# Trial.net
KiCad netlist of a schematic drawn in EAGLE
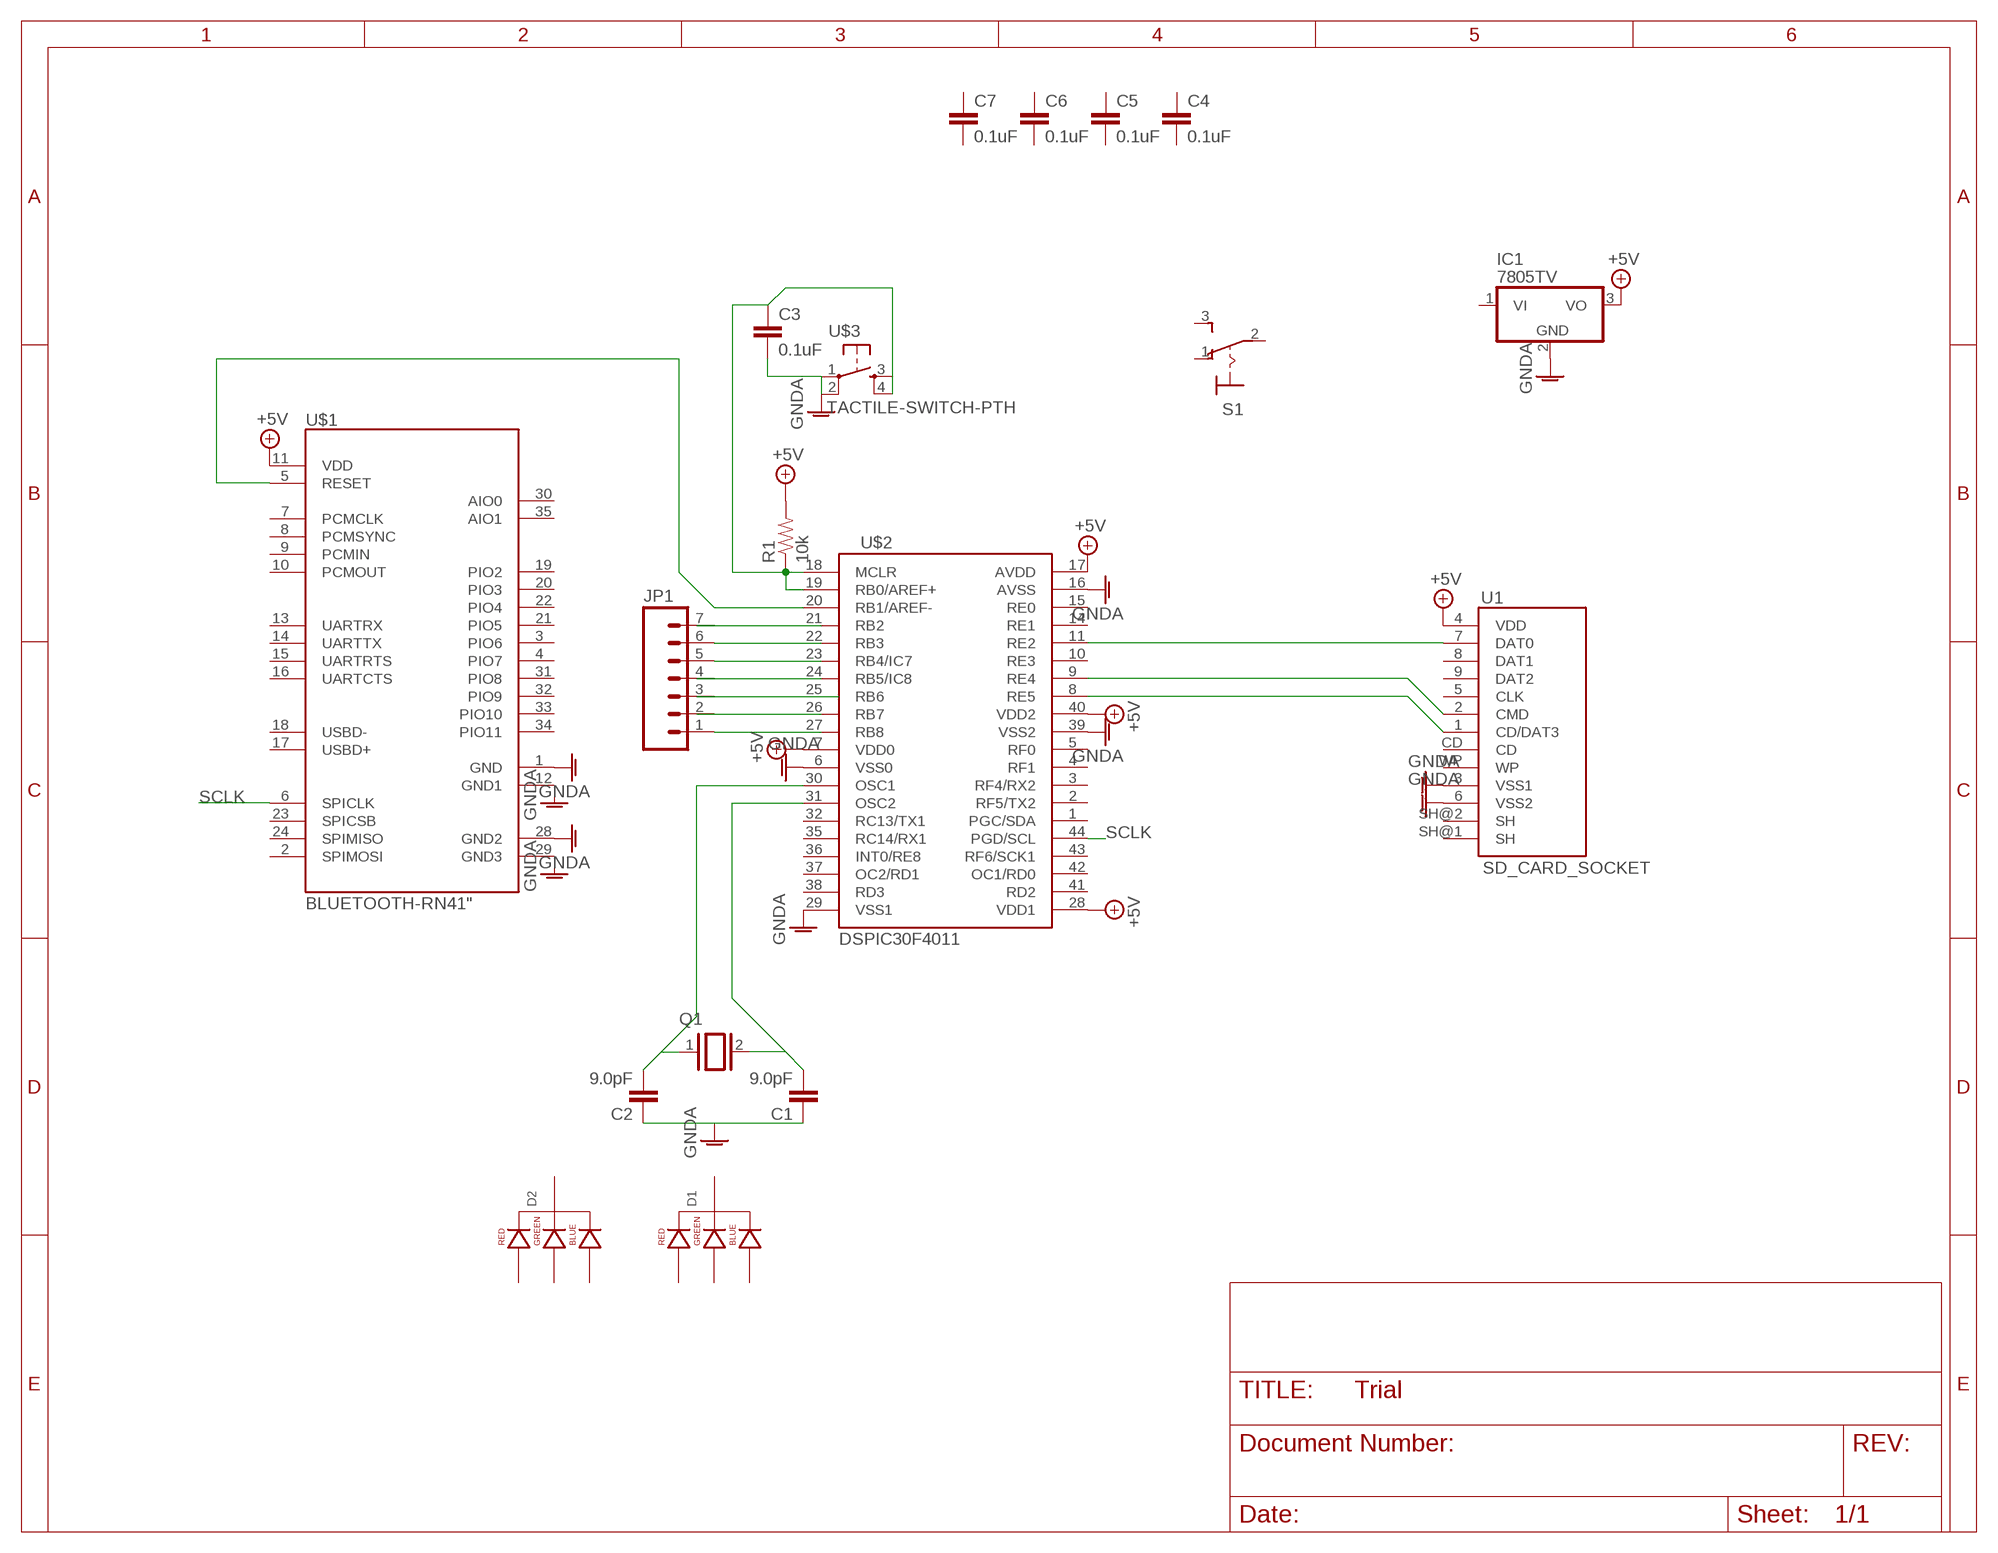
[diagram p0: schematic, sheet 1]

(export (version "E")
  (design (tool "Eeschema 10.0.6"))
  (components
    (comp (ref "C1")
      (value "9.0pF")
      (footprint "eagle-import:0603-CAP")
      (libsource (lib "eagle-import") (part "9.0PF-50V-10%(0603)"))
    )
    (comp (ref "C2")
      (value "9.0pF")
      (footprint "eagle-import:0603-CAP")
      (libsource (lib "eagle-import") (part "9.0PF-50V-10%(0603)"))
    )
    (comp (ref "C3")
      (value "0.1uF")
      (footprint "eagle-import:0402-CAP")
      (libsource (lib "eagle-import") (part "0.1UF-16V(+-10%)(0402)"))
    )
    (comp (ref "C4")
      (value "0.1uF")
      (footprint "eagle-import:0402-CAP")
      (libsource (lib "eagle-import") (part "0.1UF-16V(+-10%)(0402)"))
    )
    (comp (ref "C5")
      (value "0.1uF")
      (footprint "eagle-import:0402-CAP")
      (libsource (lib "eagle-import") (part "0.1UF-16V(+-10%)(0402)"))
    )
    (comp (ref "C6")
      (value "0.1uF")
      (footprint "eagle-import:0402-CAP")
      (libsource (lib "eagle-import") (part "0.1UF-16V(+-10%)(0402)"))
    )
    (comp (ref "C7")
      (value "0.1uF")
      (footprint "eagle-import:0402-CAP")
      (libsource (lib "eagle-import") (part "0.1UF-16V(+-10%)(0402)"))
    )
    (comp (ref "D1")
      (value "LED-RGB-CC-THRUCLEAR")
      (footprint "eagle-import:LED-RGB-THRU")
      (libsource (lib "eagle-import") (part "LED-RGB-CC-THRUCLEAR"))
    )
    (comp (ref "D2")
      (value "LED-RGB-CC-THRUCLEAR")
      (footprint "eagle-import:LED-RGB-THRU")
      (libsource (lib "eagle-import") (part "LED-RGB-CC-THRUCLEAR"))
    )
    (comp (ref "IC1")
      (value "7805TV")
      (footprint "eagle-import:TO220V")
      (libsource (lib "eagle-import") (part "78TV05"))
    )
    (comp (ref "JP1")
      (value "M07LONGPADS")
      (footprint "eagle-import:1X07_LONGPADS")
      (libsource (lib "eagle-import") (part "M07LONGPADS"))
    )
    (comp (ref "Q1")
      (value "XTAL")
      (footprint "eagle-import:Q")
      (libsource (lib "eagle-import") (part "XTAL"))
    )
    (comp (ref "R1")
      (value "10k")
      (footprint "eagle-import:AXIAL-0.3")
      (libsource (lib "eagle-import") (part "10KOHM-1/4W-1%(PTH)HORIZ"))
    )
    (comp (ref "S1")
      (value "320-916")
      (footprint "eagle-import:320-916")
      (libsource (lib "eagle-import") (part "320-916"))
    )
    (comp (ref "U$1")
      (value "BLUETOOTH-RN41\"")
      (footprint "eagle-import:RN41")
      (libsource (lib "eagle-import") (part "BLUETOOTH-RN41{dblquote}"))
    )
    (comp (ref "U$2")
      (value "DSPIC30F4011")
      (footprint "eagle-import:TQFP44")
      (libsource (lib "eagle-import") (part "DSPIC30F4011"))
    )
    (comp (ref "U$3")
      (value "TACTILE-SWITCH-PTH")
      (footprint "eagle-import:TAC-SWITCH-PTH")
      (libsource (lib "eagle-import") (part "TACTILE-SWITCH-PTH"))
    )
    (comp (ref "U1")
      (value "SD_CARD_SOCKET")
      (footprint "eagle-import:SD_1_1")
      (libsource (lib "eagle-import") (part "SD_CARD_SOCKET"))
    )
  )
  (nets
    (net (code "1") (name "+5V") (class "Default")
      (node (ref "IC1") (pin "3") (pinfunction "VO_3") (pintype "passive"))
      (node (ref "R1") (pin "P$2") (pinfunction "2_P$2") (pintype "passive"))
      (node (ref "U$1") (pin "11") (pinfunction "VDD_11") (pintype "bidirectional"))
      (node (ref "U$2") (pin "17") (pinfunction "AVDD_17") (pintype "bidirectional"))
      (node (ref "U$2") (pin "28") (pinfunction "VDD1_28") (pintype "bidirectional"))
      (node (ref "U$2") (pin "40") (pinfunction "VDD2_40") (pintype "bidirectional"))
      (node (ref "U$2") (pin "7") (pinfunction "VDD0_7") (pintype "bidirectional"))
      (node (ref "U1") (pin "4") (pinfunction "VDD_4") (pintype "power_in"))
    )
    (net (code "2") (name "/SCLK") (class "Default")
      (node (ref "U$1") (pin "6") (pinfunction "SPICLK_6") (pintype "bidirectional"))
      (node (ref "U$2") (pin "44") (pinfunction "PGD/SCL_44") (pintype "bidirectional"))
    )
    (net (code "3") (name "GNDA") (class "Default")
      (node (ref "C1") (pin "1") (pinfunction "1_1") (pintype "passive"))
      (node (ref "C2") (pin "1") (pinfunction "1_1") (pintype "passive"))
      (node (ref "C3") (pin "2") (pinfunction "2_2") (pintype "passive"))
      (node (ref "IC1") (pin "2") (pinfunction "GND_2") (pintype "passive"))
      (node (ref "U$1") (pin "1") (pinfunction "GND_1") (pintype "bidirectional"))
      (node (ref "U$1") (pin "12") (pinfunction "GND1_12") (pintype "bidirectional"))
      (node (ref "U$1") (pin "28") (pinfunction "GND2_28") (pintype "bidirectional"))
      (node (ref "U$1") (pin "29") (pinfunction "GND3_29") (pintype "bidirectional"))
      (node (ref "U$2") (pin "16") (pinfunction "AVSS_16") (pintype "bidirectional"))
      (node (ref "U$2") (pin "29") (pinfunction "VSS1_29") (pintype "bidirectional"))
      (node (ref "U$2") (pin "39") (pinfunction "VSS2_39") (pintype "bidirectional"))
      (node (ref "U$2") (pin "6") (pinfunction "VSS0_6") (pintype "bidirectional"))
      (node (ref "U$3") (pin "1") (pinfunction "1_1") (pintype "passive"))
      (node (ref "U$3") (pin "2") (pinfunction "2_2") (pintype "passive"))
      (node (ref "U1") (pin "3") (pinfunction "VSS1_3") (pintype "power_in"))
      (node (ref "U1") (pin "6") (pinfunction "VSS2_6") (pintype "power_in"))
    )
    (net (code "4") (name "Net-(R1-1)") (class "Default")
      (node (ref "C3") (pin "1") (pinfunction "1_1") (pintype "passive"))
      (node (ref "R1") (pin "P$1") (pinfunction "1_P$1") (pintype "passive"))
      (node (ref "U$2") (pin "18") (pinfunction "MCLR_18") (pintype "bidirectional"))
      (node (ref "U$2") (pin "19") (pinfunction "RB0/AREF+_19") (pintype "bidirectional"))
      (node (ref "U$3") (pin "3") (pinfunction "3_3") (pintype "passive"))
      (node (ref "U$3") (pin "4") (pinfunction "4_4") (pintype "passive"))
    )
    (net (code "5") (name "Net-(U$1-RESET)") (class "Default")
      (node (ref "U$1") (pin "5") (pinfunction "RESET_5") (pintype "bidirectional"))
      (node (ref "U$2") (pin "20") (pinfunction "RB1/AREF-_20") (pintype "bidirectional"))
    )
    (net (code "6") (name "Net-(U$2-OSC1)") (class "Default")
      (node (ref "C2") (pin "2") (pinfunction "2_2") (pintype "passive"))
      (node (ref "Q1") (pin "1") (pinfunction "1_1") (pintype "passive"))
      (node (ref "U$2") (pin "30") (pinfunction "OSC1_30") (pintype "bidirectional"))
    )
    (net (code "7") (name "Net-(U$2-OSC2)") (class "Default")
      (node (ref "C1") (pin "2") (pinfunction "2_2") (pintype "passive"))
      (node (ref "Q1") (pin "2") (pinfunction "2_2") (pintype "passive"))
      (node (ref "U$2") (pin "31") (pinfunction "OSC2_31") (pintype "bidirectional"))
    )
    (net (code "8") (name "Net-(U$2-RE2)") (class "Default")
      (node (ref "U$2") (pin "11") (pinfunction "RE2_11") (pintype "bidirectional"))
      (node (ref "U1") (pin "7") (pinfunction "DAT0_7") (pintype "bidirectional"))
    )
    (net (code "9") (name "Net-(U$2-RE4)") (class "Default")
      (node (ref "U$2") (pin "9") (pinfunction "RE4_9") (pintype "bidirectional"))
      (node (ref "U1") (pin "2") (pinfunction "CMD_2") (pintype "bidirectional"))
    )
    (net (code "10") (name "Net-(U$2-RE5)") (class "Default")
      (node (ref "U$2") (pin "8") (pinfunction "RE5_8") (pintype "bidirectional"))
      (node (ref "U1") (pin "1") (pinfunction "CD/DAT3_1") (pintype "bidirectional"))
    )
    (net (code "11") (name "unconnected-(C4-Pad1)") (class "Default")
      (node (ref "C4") (pin "1") (pinfunction "1_1") (pintype "passive"))
    )
    (net (code "12") (name "unconnected-(C4-Pad2)") (class "Default")
      (node (ref "C4") (pin "2") (pinfunction "2_2") (pintype "passive"))
    )
    (net (code "13") (name "unconnected-(C5-Pad1)") (class "Default")
      (node (ref "C5") (pin "1") (pinfunction "1_1") (pintype "passive"))
    )
    (net (code "14") (name "unconnected-(C5-Pad2)") (class "Default")
      (node (ref "C5") (pin "2") (pinfunction "2_2") (pintype "passive"))
    )
    (net (code "15") (name "unconnected-(C6-Pad1)") (class "Default")
      (node (ref "C6") (pin "1") (pinfunction "1_1") (pintype "passive"))
    )
    (net (code "16") (name "unconnected-(C6-Pad2)") (class "Default")
      (node (ref "C6") (pin "2") (pinfunction "2_2") (pintype "passive"))
    )
    (net (code "17") (name "unconnected-(C7-Pad1)") (class "Default")
      (node (ref "C7") (pin "1") (pinfunction "1_1") (pintype "passive"))
    )
    (net (code "18") (name "unconnected-(C7-Pad2)") (class "Default")
      (node (ref "C7") (pin "2") (pinfunction "2_2") (pintype "passive"))
    )
    (net (code "19") (name "unconnected-(D1-BLUE_CATHODE-Pad4)") (class "Default")
      (node (ref "D1") (pin "4") (pinfunction "BLUE_CATHODE_4") (pintype "bidirectional"))
    )
    (net (code "20") (name "unconnected-(D1-CATHODE-Pad2)") (class "Default")
      (node (ref "D1") (pin "2") (pinfunction "CATHODE_2") (pintype "bidirectional"))
    )
    (net (code "21") (name "unconnected-(D1-GREEN_CATHODE-Pad3)") (class "Default")
      (node (ref "D1") (pin "3") (pinfunction "GREEN_CATHODE_3") (pintype "bidirectional"))
    )
    (net (code "22") (name "unconnected-(D1-RED_CATHODE-Pad1)") (class "Default")
      (node (ref "D1") (pin "1") (pinfunction "RED_CATHODE_1") (pintype "bidirectional"))
    )
    (net (code "23") (name "unconnected-(D2-BLUE_CATHODE-Pad4)") (class "Default")
      (node (ref "D2") (pin "4") (pinfunction "BLUE_CATHODE_4") (pintype "bidirectional"))
    )
    (net (code "24") (name "unconnected-(D2-CATHODE-Pad2)") (class "Default")
      (node (ref "D2") (pin "2") (pinfunction "CATHODE_2") (pintype "bidirectional"))
    )
    (net (code "25") (name "unconnected-(D2-GREEN_CATHODE-Pad3)") (class "Default")
      (node (ref "D2") (pin "3") (pinfunction "GREEN_CATHODE_3") (pintype "bidirectional"))
    )
    (net (code "26") (name "unconnected-(D2-RED_CATHODE-Pad1)") (class "Default")
      (node (ref "D2") (pin "1") (pinfunction "RED_CATHODE_1") (pintype "bidirectional"))
    )
    (net (code "27") (name "unconnected-(IC1-VI-Pad1)") (class "Default")
      (node (ref "IC1") (pin "1") (pinfunction "VI_1") (pintype "input"))
    )
    (net (code "28") (name "unconnected-(JP1-Pad1)") (class "Default")
      (node (ref "JP1") (pin "1") (pinfunction "1_1") (pintype "passive"))
    )
    (net (code "29") (name "unconnected-(JP1-Pad2)") (class "Default")
      (node (ref "JP1") (pin "2") (pinfunction "2_2") (pintype "passive"))
    )
    (net (code "30") (name "unconnected-(JP1-Pad3)") (class "Default")
      (node (ref "JP1") (pin "3") (pinfunction "3_3") (pintype "passive"))
    )
    (net (code "31") (name "unconnected-(JP1-Pad4)") (class "Default")
      (node (ref "JP1") (pin "4") (pinfunction "4_4") (pintype "passive"))
    )
    (net (code "32") (name "unconnected-(JP1-Pad5)") (class "Default")
      (node (ref "JP1") (pin "5") (pinfunction "5_5") (pintype "passive"))
    )
    (net (code "33") (name "unconnected-(JP1-Pad6)") (class "Default")
      (node (ref "JP1") (pin "6") (pinfunction "6_6") (pintype "passive"))
    )
    (net (code "34") (name "unconnected-(JP1-Pad7)") (class "Default")
      (node (ref "JP1") (pin "7") (pinfunction "7_7") (pintype "passive"))
    )
    (net (code "35") (name "unconnected-(S1-O-Pad1)") (class "Default")
      (node (ref "S1") (pin "1") (pinfunction "O_1") (pintype "passive"))
    )
    (net (code "36") (name "unconnected-(S1-P-Pad2)") (class "Default")
      (node (ref "S1") (pin "2") (pinfunction "P_2") (pintype "passive"))
    )
    (net (code "37") (name "unconnected-(S1-S-Pad3)") (class "Default")
      (node (ref "S1") (pin "3") (pinfunction "S_3") (pintype "passive"))
    )
    (net (code "38") (name "unconnected-(U$1-AIO0-Pad30)") (class "Default")
      (node (ref "U$1") (pin "30") (pinfunction "AIO0_30") (pintype "bidirectional"))
    )
    (net (code "39") (name "unconnected-(U$1-AIO1-Pad35)") (class "Default")
      (node (ref "U$1") (pin "35") (pinfunction "AIO1_35") (pintype "bidirectional"))
    )
    (net (code "40") (name "unconnected-(U$1-PCMCLK-Pad7)") (class "Default")
      (node (ref "U$1") (pin "7") (pinfunction "PCMCLK_7") (pintype "bidirectional"))
    )
    (net (code "41") (name "unconnected-(U$1-PCMIN-Pad9)") (class "Default")
      (node (ref "U$1") (pin "9") (pinfunction "PCMIN_9") (pintype "bidirectional"))
    )
    (net (code "42") (name "unconnected-(U$1-PCMOUT-Pad10)") (class "Default")
      (node (ref "U$1") (pin "10") (pinfunction "PCMOUT_10") (pintype "bidirectional"))
    )
    (net (code "43") (name "unconnected-(U$1-PCMSYNC-Pad8)") (class "Default")
      (node (ref "U$1") (pin "8") (pinfunction "PCMSYNC_8") (pintype "bidirectional"))
    )
    (net (code "44") (name "unconnected-(U$1-PIO2-Pad19)") (class "Default")
      (node (ref "U$1") (pin "19") (pinfunction "PIO2_19") (pintype "bidirectional"))
    )
    (net (code "45") (name "unconnected-(U$1-PIO3-Pad20)") (class "Default")
      (node (ref "U$1") (pin "20") (pinfunction "PIO3_20") (pintype "bidirectional"))
    )
    (net (code "46") (name "unconnected-(U$1-PIO4-Pad22)") (class "Default")
      (node (ref "U$1") (pin "22") (pinfunction "PIO4_22") (pintype "bidirectional"))
    )
    (net (code "47") (name "unconnected-(U$1-PIO5-Pad21)") (class "Default")
      (node (ref "U$1") (pin "21") (pinfunction "PIO5_21") (pintype "bidirectional"))
    )
    (net (code "48") (name "unconnected-(U$1-PIO6-Pad3)") (class "Default")
      (node (ref "U$1") (pin "3") (pinfunction "PIO6_3") (pintype "bidirectional"))
    )
    (net (code "49") (name "unconnected-(U$1-PIO7-Pad4)") (class "Default")
      (node (ref "U$1") (pin "4") (pinfunction "PIO7_4") (pintype "bidirectional"))
    )
    (net (code "50") (name "unconnected-(U$1-PIO8-Pad31)") (class "Default")
      (node (ref "U$1") (pin "31") (pinfunction "PIO8_31") (pintype "bidirectional"))
    )
    (net (code "51") (name "unconnected-(U$1-PIO9-Pad32)") (class "Default")
      (node (ref "U$1") (pin "32") (pinfunction "PIO9_32") (pintype "bidirectional"))
    )
    (net (code "52") (name "unconnected-(U$1-PIO10-Pad33)") (class "Default")
      (node (ref "U$1") (pin "33") (pinfunction "PIO10_33") (pintype "bidirectional"))
    )
    (net (code "53") (name "unconnected-(U$1-PIO11-Pad34)") (class "Default")
      (node (ref "U$1") (pin "34") (pinfunction "PIO11_34") (pintype "bidirectional"))
    )
    (net (code "54") (name "unconnected-(U$1-SPICSB-Pad23)") (class "Default")
      (node (ref "U$1") (pin "23") (pinfunction "SPICSB_23") (pintype "bidirectional"))
    )
    (net (code "55") (name "unconnected-(U$1-SPIMISO-Pad24)") (class "Default")
      (node (ref "U$1") (pin "24") (pinfunction "SPIMISO_24") (pintype "bidirectional"))
    )
    (net (code "56") (name "unconnected-(U$1-SPIMOSI-Pad2)") (class "Default")
      (node (ref "U$1") (pin "2") (pinfunction "SPIMOSI_2") (pintype "bidirectional"))
    )
    (net (code "57") (name "unconnected-(U$1-UARTCTS-Pad16)") (class "Default")
      (node (ref "U$1") (pin "16") (pinfunction "UARTCTS_16") (pintype "bidirectional"))
    )
    (net (code "58") (name "unconnected-(U$1-UARTRTS-Pad15)") (class "Default")
      (node (ref "U$1") (pin "15") (pinfunction "UARTRTS_15") (pintype "bidirectional"))
    )
    (net (code "59") (name "unconnected-(U$1-UARTRX-Pad13)") (class "Default")
      (node (ref "U$1") (pin "13") (pinfunction "UARTRX_13") (pintype "bidirectional"))
    )
    (net (code "60") (name "unconnected-(U$1-UARTTX-Pad14)") (class "Default")
      (node (ref "U$1") (pin "14") (pinfunction "UARTTX_14") (pintype "bidirectional"))
    )
    (net (code "61") (name "unconnected-(U$1-USBD+-Pad17)") (class "Default")
      (node (ref "U$1") (pin "17") (pinfunction "USBD+_17") (pintype "bidirectional"))
    )
    (net (code "62") (name "unconnected-(U$1-USBD--Pad18)") (class "Default")
      (node (ref "U$1") (pin "18") (pinfunction "USBD-_18") (pintype "bidirectional"))
    )
    (net (code "63") (name "unconnected-(U$2-INT0{slash}RE8-Pad36)") (class "Default")
      (node (ref "U$2") (pin "36") (pinfunction "INT0/RE8_36") (pintype "bidirectional"))
    )
    (net (code "64") (name "unconnected-(U$2-OC1{slash}RD0-Pad42)") (class "Default")
      (node (ref "U$2") (pin "42") (pinfunction "OC1/RD0_42") (pintype "bidirectional"))
    )
    (net (code "65") (name "unconnected-(U$2-OC2{slash}RD1-Pad37)") (class "Default")
      (node (ref "U$2") (pin "37") (pinfunction "OC2/RD1_37") (pintype "bidirectional"))
    )
    (net (code "66") (name "unconnected-(U$2-PGC{slash}SDA-Pad1)") (class "Default")
      (node (ref "U$2") (pin "1") (pinfunction "PGC/SDA_1") (pintype "bidirectional"))
    )
    (net (code "67") (name "unconnected-(U$2-RB2-Pad21)") (class "Default")
      (node (ref "U$2") (pin "21") (pinfunction "RB2_21") (pintype "bidirectional"))
    )
    (net (code "68") (name "unconnected-(U$2-RB3-Pad22)") (class "Default")
      (node (ref "U$2") (pin "22") (pinfunction "RB3_22") (pintype "bidirectional"))
    )
    (net (code "69") (name "unconnected-(U$2-RB4{slash}IC7-Pad23)") (class "Default")
      (node (ref "U$2") (pin "23") (pinfunction "RB4/IC7_23") (pintype "bidirectional"))
    )
    (net (code "70") (name "unconnected-(U$2-RB5{slash}IC8-Pad24)") (class "Default")
      (node (ref "U$2") (pin "24") (pinfunction "RB5/IC8_24") (pintype "bidirectional"))
    )
    (net (code "71") (name "unconnected-(U$2-RB6-Pad25)") (class "Default")
      (node (ref "U$2") (pin "25") (pinfunction "RB6_25") (pintype "bidirectional"))
    )
    (net (code "72") (name "unconnected-(U$2-RB7-Pad26)") (class "Default")
      (node (ref "U$2") (pin "26") (pinfunction "RB7_26") (pintype "bidirectional"))
    )
    (net (code "73") (name "unconnected-(U$2-RB8-Pad27)") (class "Default")
      (node (ref "U$2") (pin "27") (pinfunction "RB8_27") (pintype "bidirectional"))
    )
    (net (code "74") (name "unconnected-(U$2-RC13{slash}TX1-Pad32)") (class "Default")
      (node (ref "U$2") (pin "32") (pinfunction "RC13/TX1_32") (pintype "bidirectional"))
    )
    (net (code "75") (name "unconnected-(U$2-RC14{slash}RX1-Pad35)") (class "Default")
      (node (ref "U$2") (pin "35") (pinfunction "RC14/RX1_35") (pintype "bidirectional"))
    )
    (net (code "76") (name "unconnected-(U$2-RD2-Pad41)") (class "Default")
      (node (ref "U$2") (pin "41") (pinfunction "RD2_41") (pintype "bidirectional"))
    )
    (net (code "77") (name "unconnected-(U$2-RD3-Pad38)") (class "Default")
      (node (ref "U$2") (pin "38") (pinfunction "RD3_38") (pintype "bidirectional"))
    )
    (net (code "78") (name "unconnected-(U$2-RE0-Pad15)") (class "Default")
      (node (ref "U$2") (pin "15") (pinfunction "RE0_15") (pintype "bidirectional"))
    )
    (net (code "79") (name "unconnected-(U$2-RE1-Pad14)") (class "Default")
      (node (ref "U$2") (pin "14") (pinfunction "RE1_14") (pintype "bidirectional"))
    )
    (net (code "80") (name "unconnected-(U$2-RE3-Pad10)") (class "Default")
      (node (ref "U$2") (pin "10") (pinfunction "RE3_10") (pintype "bidirectional"))
    )
    (net (code "81") (name "unconnected-(U$2-RF0-Pad5)") (class "Default")
      (node (ref "U$2") (pin "5") (pinfunction "RF0_5") (pintype "bidirectional"))
    )
    (net (code "82") (name "unconnected-(U$2-RF1-Pad4)") (class "Default")
      (node (ref "U$2") (pin "4") (pinfunction "RF1_4") (pintype "bidirectional"))
    )
    (net (code "83") (name "unconnected-(U$2-RF4{slash}RX2-Pad3)") (class "Default")
      (node (ref "U$2") (pin "3") (pinfunction "RF4/RX2_3") (pintype "bidirectional"))
    )
    (net (code "84") (name "unconnected-(U$2-RF5{slash}TX2-Pad2)") (class "Default")
      (node (ref "U$2") (pin "2") (pinfunction "RF5/TX2_2") (pintype "bidirectional"))
    )
    (net (code "85") (name "unconnected-(U$2-RF6{slash}SCK1-Pad43)") (class "Default")
      (node (ref "U$2") (pin "43") (pinfunction "RF6/SCK1_43") (pintype "bidirectional"))
    )
    (net (code "86") (name "unconnected-(U1-CLK-Pad5)") (class "Default")
      (node (ref "U1") (pin "5") (pinfunction "CLK_5") (pintype "bidirectional"))
    )
    (net (code "87") (name "unconnected-(U1-DAT1-Pad8)") (class "Default")
      (node (ref "U1") (pin "8") (pinfunction "DAT1_8") (pintype "bidirectional"))
    )
    (net (code "88") (name "unconnected-(U1-DAT2-Pad9)") (class "Default")
      (node (ref "U1") (pin "9") (pinfunction "DAT2_9") (pintype "bidirectional"))
    )
    (net (code "89") (name "unconnected-(U1-PadCD)") (class "Default")
      (node (ref "U1") (pin "CD") (pinfunction "CD_CD") (pintype "bidirectional"))
    )
    (net (code "90") (name "unconnected-(U1-PadWP)") (class "Default")
      (node (ref "U1") (pin "WP") (pinfunction "WP_WP") (pintype "bidirectional"))
    )
    (net (code "91") (name "unconnected-(U1-SH-PadSH@1)") (class "Default")
      (node (ref "U1") (pin "SH@1") (pinfunction "SH_SH@1") (pintype "bidirectional"))
    )
    (net (code "92") (name "unconnected-(U1-SH-PadSH@2)") (class "Default")
      (node (ref "U1") (pin "SH@2") (pinfunction "SH_SH@2") (pintype "bidirectional"))
    )
  )
)
